# Stirplate.net
KiCad netlist of a schematic drawn in EAGLE
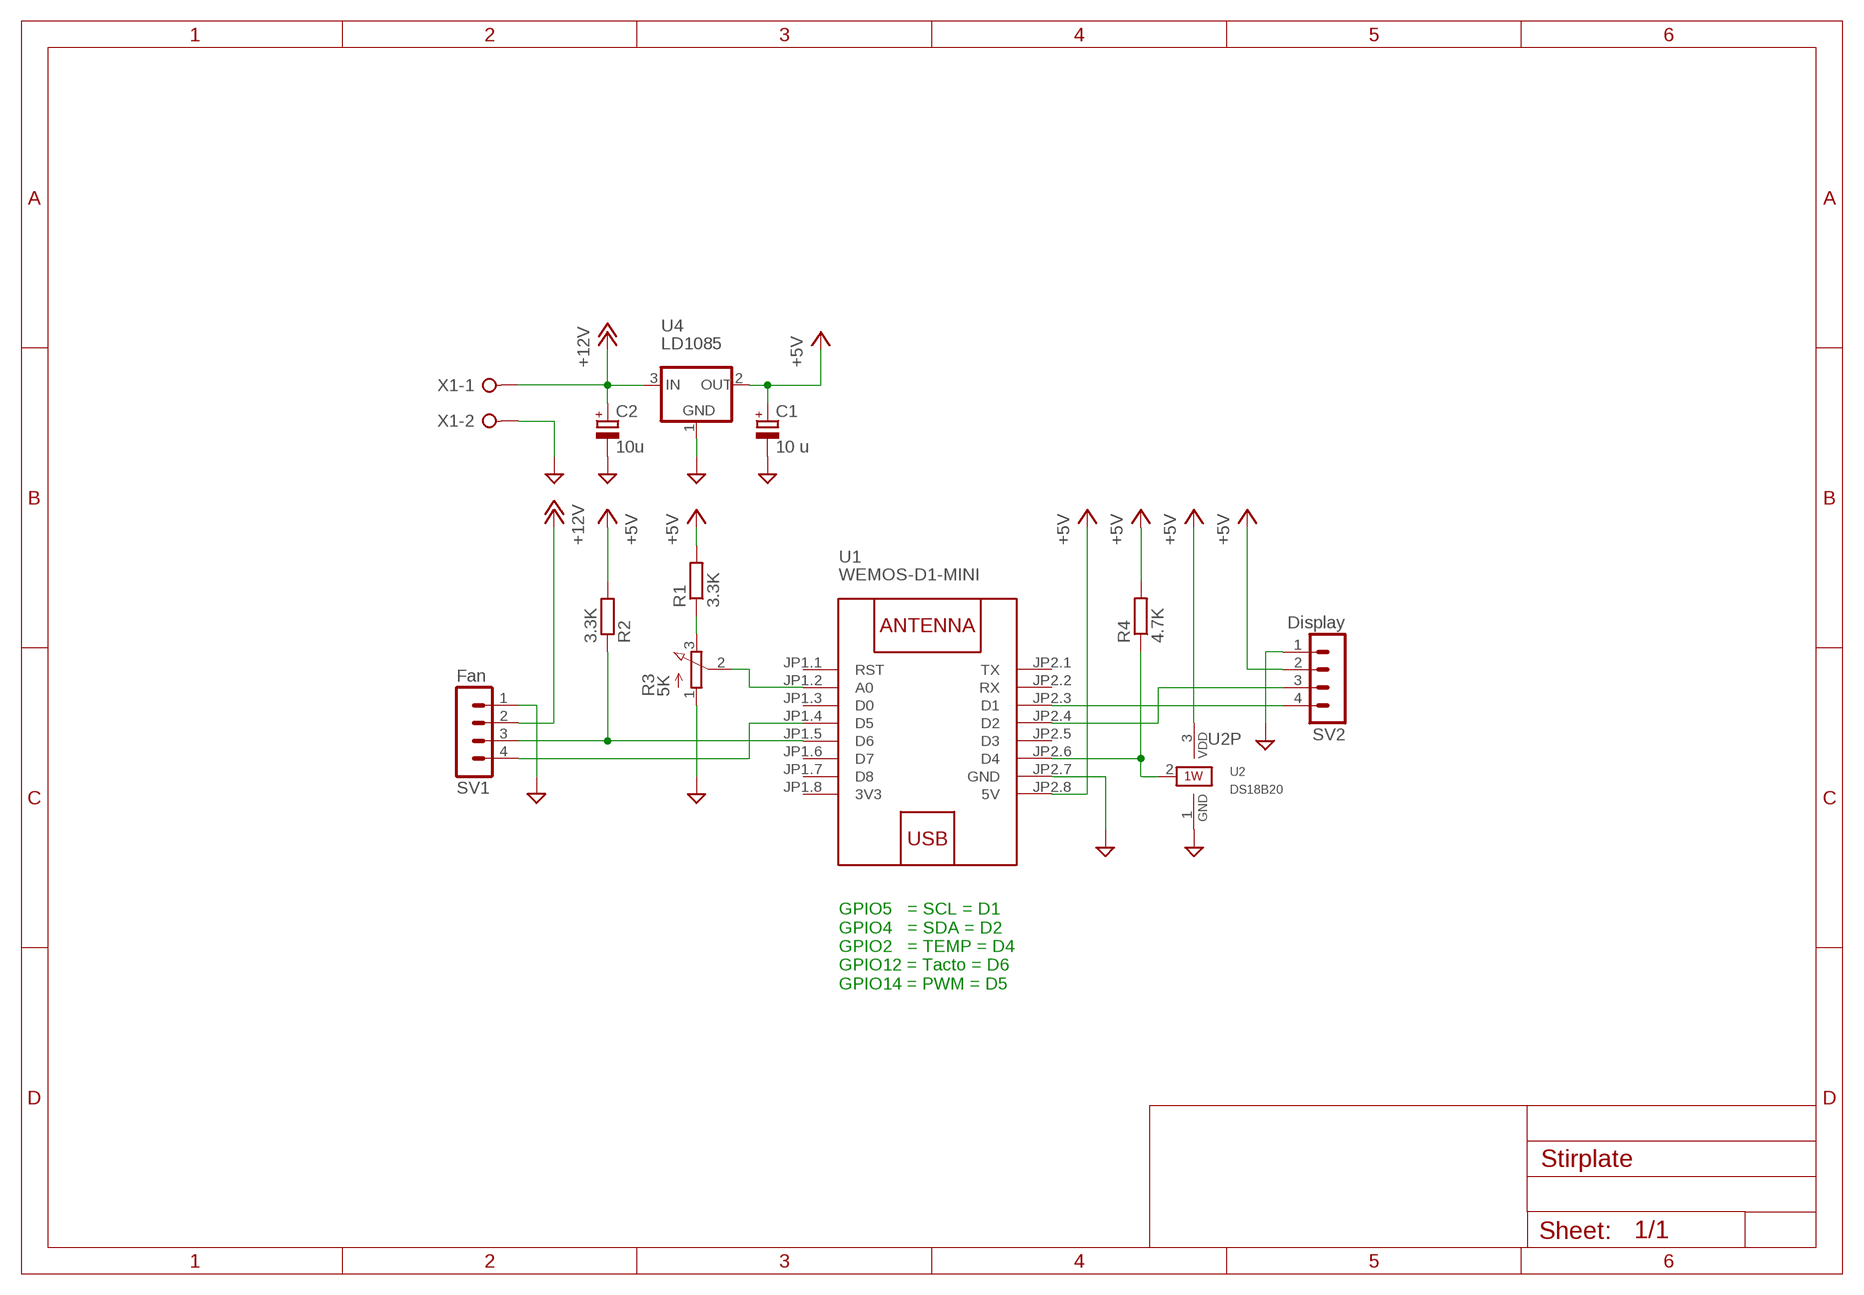
[diagram p0: schematic, sheet 1]

(export (version "E")
  (design (tool "Eeschema 10.0.6"))
  (components
    (comp (ref "C1")
      (value "10 u")
      (footprint "eagle-import:E2,5-5")
      (libsource (lib "eagle-import") (part "CPOL-EUE2.5-5"))
    )
    (comp (ref "C2")
      (value "10u")
      (footprint "eagle-import:E2,5-5")
      (libsource (lib "eagle-import") (part "CPOL-EUE2.5-5"))
    )
    (comp (ref "R1")
      (value "3.3K")
      (footprint "eagle-import:0207_10")
      (libsource (lib "eagle-import") (part "R-EU_0207/10"))
    )
    (comp (ref "R2")
      (value "3.3K")
      (footprint "eagle-import:0207_10")
      (libsource (lib "eagle-import") (part "R-EU_0207/10"))
    )
    (comp (ref "R3")
      (value "5K")
      (footprint "eagle-import:3RP_1610N")
      (libsource (lib "eagle-import") (part "3RP/1610N"))
    )
    (comp (ref "R4")
      (value "4.7K")
      (footprint "eagle-import:0207_10")
      (libsource (lib "eagle-import") (part "R-EU_0207/10"))
    )
    (comp (ref "SV1")
      (value "Fan")
      (footprint "eagle-import:MA04-1")
      (libsource (lib "eagle-import") (part "MA04-1"))
    )
    (comp (ref "SV2")
      (value "Display")
      (footprint "eagle-import:MA04-1")
      (libsource (lib "eagle-import") (part "MA04-1"))
    )
    (comp (ref "U1")
      (value "WEMOS-D1-MINI")
      (footprint "eagle-import:WEMOS-D1-MINI")
      (libsource (lib "eagle-import") (part "WEMOS-D1-MINI"))
    )
    (comp (ref "U2")
      (value "DS18B20")
      (footprint "eagle-import:TO92-")
      (libsource (lib "eagle-import") (part "DS18B20"))
    )
    (comp (ref "U4")
      (value "PMX42_LD1086VXX-H")
      (footprint "eagle-import:PMX42_TO220-NH")
      (fields (field (name "ID") "LD1085"))
      (libsource (lib "eagle-import") (part "PMX42_LD1086VXX-H"))
    )
    (comp (ref "X1")
      (value "W237-02P")
      (footprint "eagle-import:W237-132")
      (libsource (lib "eagle-import") (part "W237-02P"))
    )
  )
  (nets
    (net (code "1") (name "+5V") (class "Default")
      (node (ref "C1") (pin "+") (pinfunction "+_+") (pintype "passive"))
      (node (ref "R1") (pin "2") (pinfunction "2_2") (pintype "passive"))
      (node (ref "R2") (pin "2") (pinfunction "2_2") (pintype "passive"))
      (node (ref "R4") (pin "2") (pinfunction "2_2") (pintype "passive"))
      (node (ref "SV2") (pin "2") (pinfunction "2_2") (pintype "passive"))
      (node (ref "U1") (pin "JP2.8") (pinfunction "5V_JP2.8") (pintype "power_in"))
      (node (ref "U2") (pin "3") (pinfunction "VDD_3") (pintype "power_in"))
      (node (ref "U4") (pin "2") (pinfunction "OUT_2") (pintype "passive"))
    )
    (net (code "2") (name "+12V") (class "Default")
      (node (ref "C2") (pin "+") (pinfunction "+_+") (pintype "passive"))
      (node (ref "SV1") (pin "2") (pinfunction "2_2") (pintype "passive"))
      (node (ref "U4") (pin "3") (pinfunction "IN_3") (pintype "input"))
      (node (ref "X1") (pin "1") (pinfunction "KL_1") (pintype "passive"))
    )
    (net (code "3") (name "/3V3") (class "Default")
      (node (ref "U1") (pin "JP1.8") (pinfunction "3V3_JP1.8") (pintype "power_in"))
    )
    (net (code "4") (name "GND") (class "Default")
      (node (ref "C1") (pin "-") (pinfunction "-_-") (pintype "passive"))
      (node (ref "C2") (pin "-") (pinfunction "-_-") (pintype "passive"))
      (node (ref "R3") (pin "1") (pinfunction "A_1") (pintype "passive"))
      (node (ref "SV1") (pin "1") (pinfunction "1_1") (pintype "passive"))
      (node (ref "SV2") (pin "1") (pinfunction "1_1") (pintype "passive"))
      (node (ref "U1") (pin "JP2.7") (pinfunction "GND_JP2.7") (pintype "power_in"))
      (node (ref "U2") (pin "1") (pinfunction "GND_1") (pintype "power_in"))
      (node (ref "U4") (pin "1") (pinfunction "GND_1") (pintype "input"))
      (node (ref "X1") (pin "2") (pinfunction "KL_2") (pintype "passive"))
    )
    (net (code "5") (name "Net-(R3-E)") (class "Default")
      (node (ref "R1") (pin "1") (pinfunction "1_1") (pintype "passive"))
      (node (ref "R3") (pin "3") (pinfunction "E_3") (pintype "passive"))
    )
    (net (code "6") (name "Net-(R3-S)") (class "Default")
      (node (ref "R3") (pin "2") (pinfunction "S_2") (pintype "passive"))
      (node (ref "U1") (pin "JP1.2") (pinfunction "A0_JP1.2") (pintype "bidirectional"))
    )
    (net (code "7") (name "Net-(U1-D1)") (class "Default")
      (node (ref "SV2") (pin "4") (pinfunction "4_4") (pintype "passive"))
      (node (ref "U1") (pin "JP2.3") (pinfunction "D1_JP2.3") (pintype "bidirectional"))
    )
    (net (code "8") (name "Net-(U1-D2)") (class "Default")
      (node (ref "SV2") (pin "3") (pinfunction "3_3") (pintype "passive"))
      (node (ref "U1") (pin "JP2.4") (pinfunction "D2_JP2.4") (pintype "bidirectional"))
    )
    (net (code "9") (name "Net-(U1-D4)") (class "Default")
      (node (ref "R4") (pin "1") (pinfunction "1_1") (pintype "passive"))
      (node (ref "U1") (pin "JP2.6") (pinfunction "D4_JP2.6") (pintype "bidirectional"))
      (node (ref "U2") (pin "2") (pinfunction "1W_2") (pintype "power_in"))
    )
    (net (code "10") (name "Net-(U1-D5)") (class "Default")
      (node (ref "SV1") (pin "4") (pinfunction "4_4") (pintype "passive"))
      (node (ref "U1") (pin "JP1.4") (pinfunction "D5_JP1.4") (pintype "bidirectional"))
    )
    (net (code "11") (name "Net-(U1-D6)") (class "Default")
      (node (ref "R2") (pin "1") (pinfunction "1_1") (pintype "passive"))
      (node (ref "SV1") (pin "3") (pinfunction "3_3") (pintype "passive"))
      (node (ref "U1") (pin "JP1.5") (pinfunction "D6_JP1.5") (pintype "bidirectional"))
    )
    (net (code "12") (name "unconnected-(U1-D0-PadJP1.3)") (class "Default")
      (node (ref "U1") (pin "JP1.3") (pinfunction "D0_JP1.3") (pintype "bidirectional"))
    )
    (net (code "13") (name "unconnected-(U1-D3-PadJP2.5)") (class "Default")
      (node (ref "U1") (pin "JP2.5") (pinfunction "D3_JP2.5") (pintype "bidirectional"))
    )
    (net (code "14") (name "unconnected-(U1-D7-PadJP1.6)") (class "Default")
      (node (ref "U1") (pin "JP1.6") (pinfunction "D7_JP1.6") (pintype "bidirectional"))
    )
    (net (code "15") (name "unconnected-(U1-D8-PadJP1.7)") (class "Default")
      (node (ref "U1") (pin "JP1.7") (pinfunction "D8_JP1.7") (pintype "bidirectional"))
    )
    (net (code "16") (name "unconnected-(U1-RST-PadJP1.1)") (class "Default")
      (node (ref "U1") (pin "JP1.1") (pinfunction "RST_JP1.1") (pintype "bidirectional"))
    )
    (net (code "17") (name "unconnected-(U1-RX-PadJP2.2)") (class "Default")
      (node (ref "U1") (pin "JP2.2") (pinfunction "RX_JP2.2") (pintype "bidirectional"))
    )
    (net (code "18") (name "unconnected-(U1-TX-PadJP2.1)") (class "Default")
      (node (ref "U1") (pin "JP2.1") (pinfunction "TX_JP2.1") (pintype "bidirectional"))
    )
  )
)
